# Sheet1.net
KiCad netlist of a schematic drawn in Altium Designer
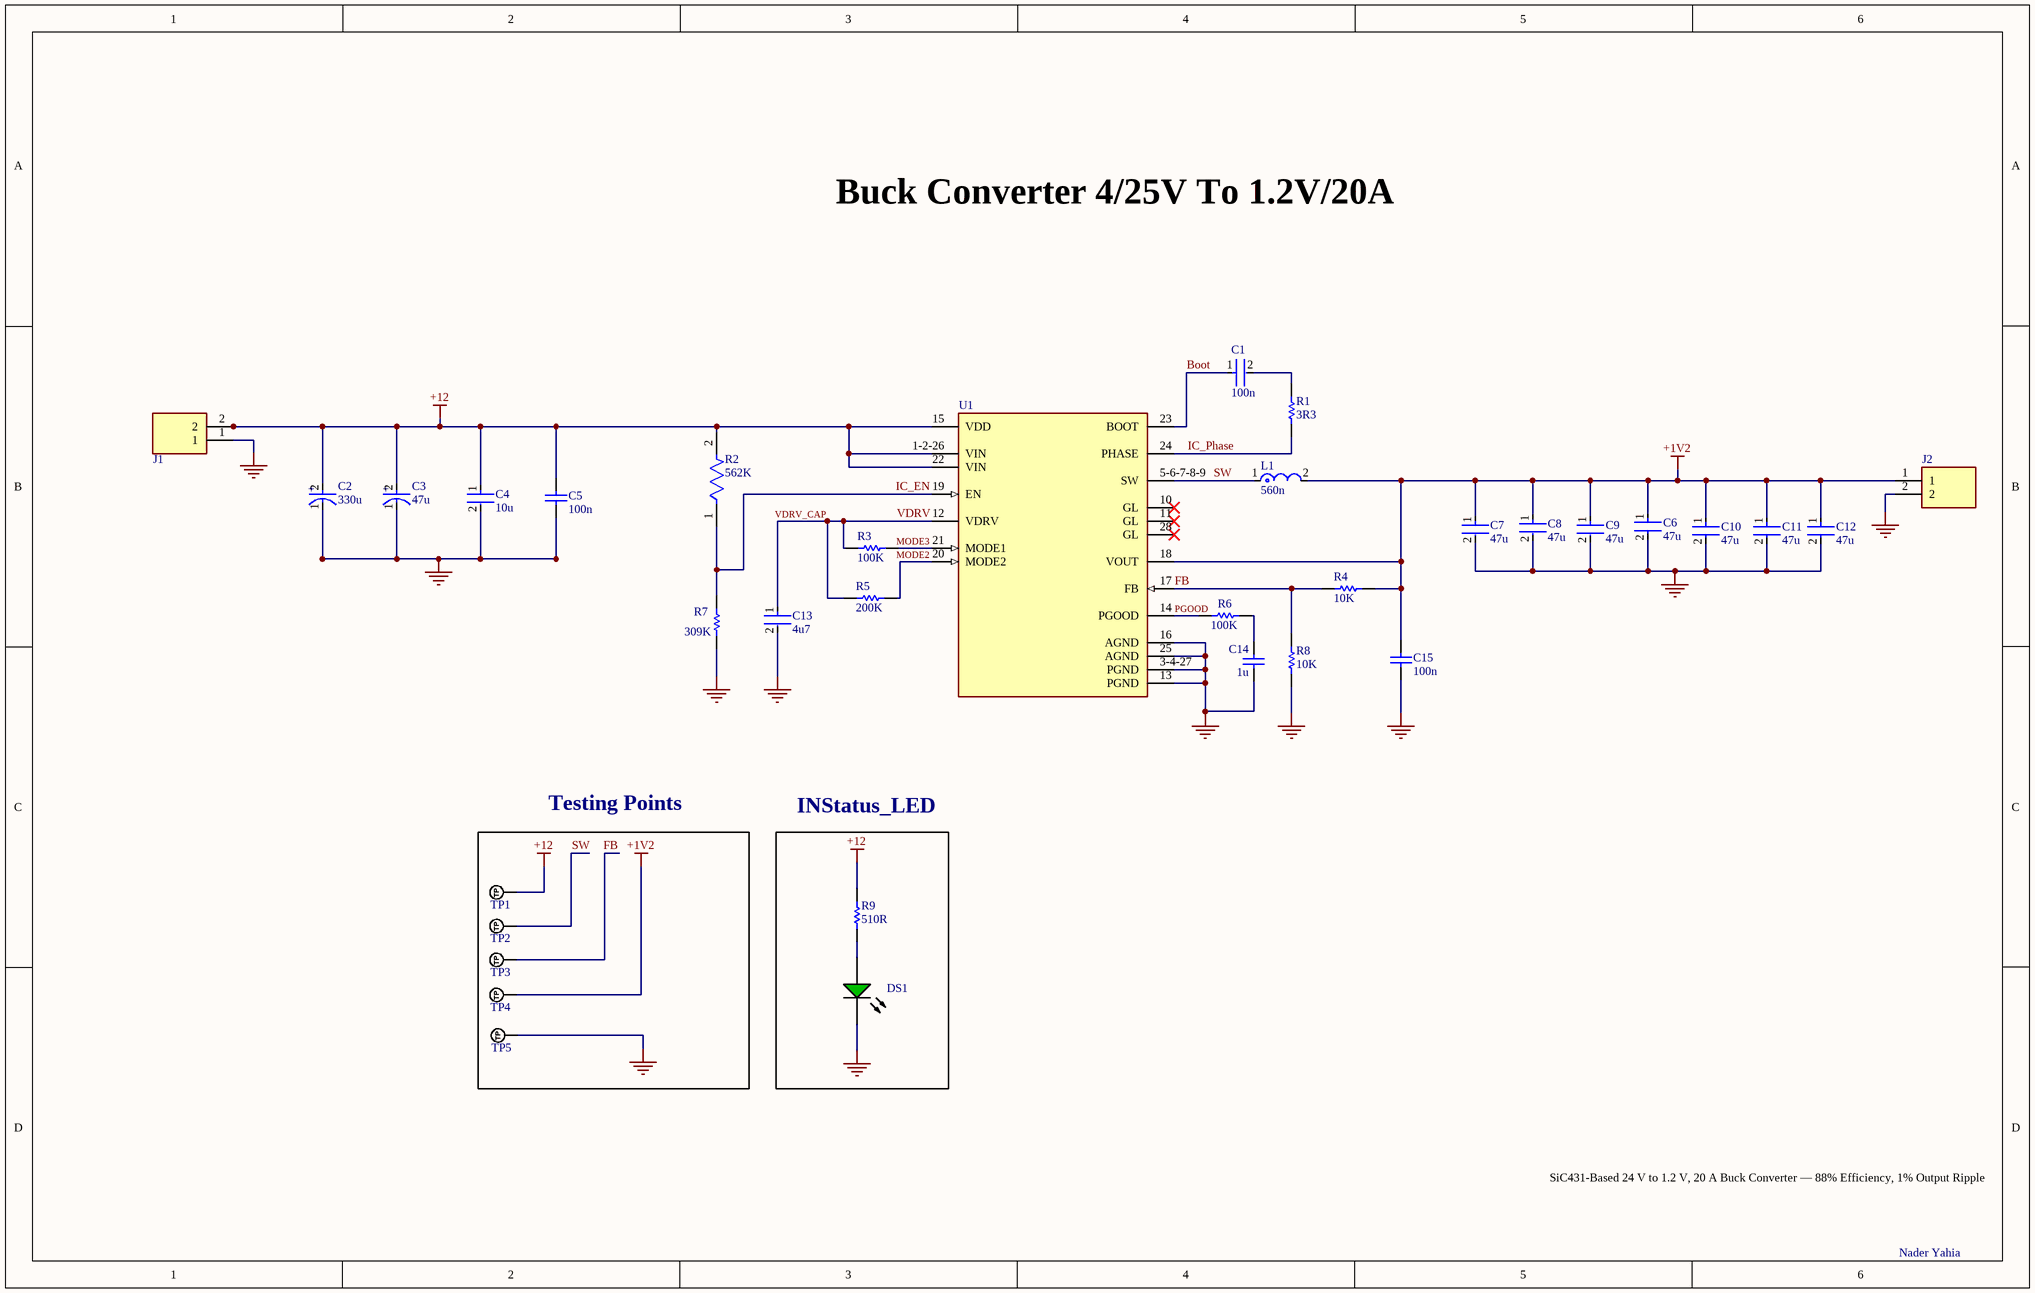
[diagram p0: Sheet1.SchDoc]

(export (version "E")
  (design (tool "Eeschema 10.0.6"))
  (components
    (comp (ref "C1")
      (value "100n")
      (footprint "FP-C0402-BB-MFG")
      (description "C0402 0.10 μF X5R 10.00% 10 V")
      (fields
        (field (name "MANUFACTURER_PART_NUMBER") "C0402C104K8PAC")
        (field (name "MANUFACTURER") "Kemet")
      )
      (libsource (lib "Altium Content Vault") (part "b4654b650e69147ec39a6b967a45e02"))
    )
    (comp (ref "C2")
      (value "330u")
      (footprint "FP-PCR1V331MCL1GS-MFG")
      (description "CAP ALUM POLY 330UF 20% 35V SMD")
      (fields
        (field (name "MANUFACTURER") "Nichicon")
        (field (name "OCTOPART") "https://octopart.com/pcr1v331mcl1gs-nichicon-34508554")
      )
      (libsource (lib "Altium Content Vault") (part "cf48714ba7e38822c1575c7ec0b6d1f"))
    )
    (comp (ref "C3")
      (value "47u")
      (footprint "FP-FPD-MFG")
      (description "CAP ALUM 47UF 20% 35V SMD")
      (fields (field (name "TOLERANCE") "20%") (field (name "VOLTAGE") "35V"))
      (libsource (lib "Altium Content Vault") (part "cf48714ba7e38822c1575c7ec0b6d1f"))
    )
    (comp (ref "C4")
      (value "10u")
      (footprint "FP-CL32-IPC_C")
      (description "Cap Ceramic 10uF 50V X7R ±10% SMD 1210 +125°C Embossed T/R")
      (fields (field (name "TOLERANCE") "10%") (field (name "VOLTAGE") "50V"))
      (libsource (lib "Altium Content Vault") (part "b4654b650e69147ec39a6b967a45e02"))
    )
    (comp (ref "C5")
      (value "100n")
      (footprint "CAPC1608X95X40NL15T15")
      (fields
        (field (name "MANUFACTURER") "Vitramon")
        (field (name "MANUFACTURER_PART_NUMBER") "VJ0603Y104KXJCW1BC")
      )
      (libsource (lib "Altium Content Vault") (part "CAP"))
    )
    (comp (ref "C6")
      (value "47u")
      (footprint "FP-GRM32E-0_3-0_2-IPC_A")
      (description "Chip Multilayer Ceramic Capacitors for General Purpose, 1210, 47uF, X7R, 15%, 10%, 10V")
      (fields (field (name "TOLERANCE") "10%") (field (name "VOLTAGE") "10V"))
      (libsource (lib "Altium Content Vault") (part "02cd4be3c70576c341d710602a673aa"))
    )
    (comp (ref "C7")
      (value "47u")
      (footprint "FP-GRM32E-0_3-0_2-IPC_A")
      (description "Chip Multilayer Ceramic Capacitors for General Purpose, 1210, 47uF, X7R, 15%, 10%, 10V")
      (fields (field (name "TOLERANCE") "10%") (field (name "VOLTAGE") "10V"))
      (libsource (lib "Altium Content Vault") (part "02cd4be3c70576c341d710602a673aa"))
    )
    (comp (ref "C8")
      (value "47u")
      (footprint "FP-GRM32E-0_3-0_2-IPC_A")
      (description "Chip Multilayer Ceramic Capacitors for General Purpose, 1210, 47uF, X7R, 15%, 10%, 10V")
      (fields (field (name "TOLERANCE") "10%") (field (name "VOLTAGE") "10V"))
      (libsource (lib "Altium Content Vault") (part "02cd4be3c70576c341d710602a673aa"))
    )
    (comp (ref "C9")
      (value "47u")
      (footprint "FP-GRM32E-0_3-0_2-IPC_A")
      (description "Chip Multilayer Ceramic Capacitors for General Purpose, 1210, 47uF, X7R, 15%, 10%, 10V")
      (fields (field (name "TOLERANCE") "10%") (field (name "VOLTAGE") "10V"))
      (libsource (lib "Altium Content Vault") (part "02cd4be3c70576c341d710602a673aa"))
    )
    (comp (ref "C10")
      (value "47u")
      (footprint "FP-GRM32E-0_3-0_2-IPC_A")
      (description "Chip Multilayer Ceramic Capacitors for General Purpose, 1210, 47uF, X7R, 15%, 10%, 10V")
      (fields (field (name "TOLERANCE") "10%") (field (name "VOLTAGE") "10V"))
      (libsource (lib "Altium Content Vault") (part "02cd4be3c70576c341d710602a673aa"))
    )
    (comp (ref "C11")
      (value "47u")
      (footprint "FP-GRM32E-0_3-0_2-IPC_A")
      (description "Chip Multilayer Ceramic Capacitors for General Purpose, 1210, 47uF, X7R, 15%, 10%, 10V")
      (fields (field (name "TOLERANCE") "10%") (field (name "VOLTAGE") "10V"))
      (libsource (lib "Altium Content Vault") (part "02cd4be3c70576c341d710602a673aa"))
    )
    (comp (ref "C12")
      (value "47u")
      (footprint "FP-GRM32E-0_3-0_2-IPC_A")
      (description "Chip Multilayer Ceramic Capacitors for General Purpose, 1210, 47uF, X7R, 15%, 10%, 10V")
      (fields (field (name "TOLERANCE") "10%") (field (name "VOLTAGE") "10V"))
      (libsource (lib "Altium Content Vault") (part "02cd4be3c70576c341d710602a673aa"))
    )
    (comp (ref "C13")
      (value "4u7")
      (footprint "FP-CC0603-DA-MFG")
      (description "CAP CER 4.7UF 6.3V X5R 0603")
      (fields (field (name "TOLERANCE") "0.1") (field (name "MANUFACTURER_PART_NUMBER") "CC0603KRX5R5BB475"))
      (libsource (lib "Altium Content Vault") (part "11868f565c42a9108669ba33697ecf6"))
    )
    (comp (ref "C14")
      (value "1u")
      (footprint "CAPC1608X95X40NL15T15")
      (fields
        (field (name "MANUFACTURER") "Vitramon")
        (field (name "MANUFACTURER_PART_NUMBER") "VJ0603G105KXYCW1BC")
      )
      (libsource (lib "Altium Content Vault") (part "CAP"))
    )
    (comp (ref "C15")
      (value "100n")
      (footprint "CAPC1608X95X40NL15T15")
      (fields
        (field (name "MANUFACTURER") "Vitramon")
        (field (name "MANUFACTURER_PART_NUMBER") "VJ0603Y104KXJCW1BC")
      )
      (libsource (lib "Altium Content Vault") (part "CAP"))
    )
    (comp (ref "DS1")
      (value "LTST-C170KGKT")
      (footprint "LTST-LTST-C170KGKT-2_V")
      (description "Ultra Bright AlInGaP Chip LED, 75 mW, -55 to 85 degC, 2-Pin SMD (0805), RoHS, Tape and Reel")
      (fields (field (name "MANUFACTURER") "Lite-On"))
      (libsource (lib "Altium Content Vault") (part "LED-GREEN-KA-2"))
    )
    (comp (ref "J1")
      (value "TB005-762-02BE")
      (footprint "SamacSys:TB00576202BE")
      (description "Connector")
      (fields (field (name "MOUSER PART NUMBER") "490-TB005-762-02BE"))
      (libsource (lib "") (part "TB005-762-02BE_1"))
    )
    (comp (ref "J2")
      (value "TB005-762-02BE")
      (footprint "SamacSys:TB00576202BE")
      (description "Connector")
      (fields (field (name "MOUSER PART NUMBER") "490-TB005-762-02BE"))
      (libsource (lib "*") (part "TB005-762-02BE"))
    )
    (comp (ref "L1")
      (value "560n")
      (footprint "FP-FCUL1060-MFG")
      (description "FIXED IND")
      (fields (field (name "MANUFACTURER_PART_NUMBER") "FCUL1060-H-R56M=P3"))
      (libsource (lib "Altium Content Vault") (part "4cc4b267dca4c8e51f7102f422741d8"))
    )
    (comp (ref "R1")
      (value "3R3")
      (footprint "RESC1005X40X25LL05T10")
      (fields
        (field (name "MANUFACTURER_PART_NUMBER") "RC0402FR-0733RL")
        (field (name "MANUFACTURER") "Yageo / Phycomp")
      )
      (libsource (lib "Altium Content Vault") (part "RES"))
    )
    (comp (ref "R2")
      (value "562K")
      (footprint "FP-CRCW0402-e3-MFG")
      (description "RES Thick Film, 562kΩ, 1%, 0.063W, 100ppm/°C, 0402")
      (fields (field (name "TOLERANCE") "1%") (field (name "MANUFACTURER_PART_NUMBER") "CRCW0402562KFKED"))
      (libsource (lib "Altium Content Vault") (part "1029c3af85768c4190bb7ad29bc67b5"))
    )
    (comp (ref "R3")
      (value "100K")
      (footprint "RESC1005X40X25NL05T10")
      (fields
        (field (name "MANUFACTURER_PART_NUMBER") "RC0402FR-07100KL")
        (field (name "MANUFACTURER") "Yageo / Phycomp")
      )
      (libsource (lib "Altium Content Vault") (part "RES"))
    )
    (comp (ref "R4")
      (value "10K")
      (footprint "RESC1609X50X30NL8T20")
      (description "Chip Resistor, 10 KOhm, +/- 1%, 100 mW, -55 to 155 degC, 0603 (1608 Metric), RoHS, Tape and Reel")
      (fields
        (field (name "MANUFACTURER") "Vishay Semiconductor")
        (field (name "MANUFACTURER_PART_NUMBER") "CRCW060310K0FKEA")
      )
      (libsource (lib "Altium Content Vault") (part "RES-2"))
    )
    (comp (ref "R5")
      (value "200K")
      (footprint "RESC1005X40X25LL05T10")
      (fields
        (field (name "MANUFACTURER_PART_NUMBER") "RC0402FR-07200KL")
        (field (name "MANUFACTURER") "Yageo / Phycomp")
      )
      (libsource (lib "Altium Content Vault") (part "RES"))
    )
    (comp (ref "R6")
      (value "100K")
      (footprint "RESC1005X40X25NL05T10")
      (fields
        (field (name "MANUFACTURER_PART_NUMBER") "RC0402FR-07100KL")
        (field (name "MANUFACTURER") "Yageo / Phycomp")
      )
      (libsource (lib "Altium Content Vault") (part "RES"))
    )
    (comp (ref "R7")
      (value "309K")
      (footprint "RESC1005X40X25LL05T10")
      (fields
        (field (name "MANUFACTURER") "Yageo")
        (field (name "MANUFACTURER_PART_NUMBER") "RC0402FR-07309KL")
      )
      (libsource (lib "Altium Content Vault") (part "RES"))
    )
    (comp (ref "R8")
      (value "10K")
      (footprint "RESC1609X50X30NL8T20")
      (description "Chip Resistor, 10 KOhm, +/- 1%, 100 mW, -55 to 155 degC, 0603 (1608 Metric), RoHS, Tape and Reel")
      (fields
        (field (name "MANUFACTURER") "Vishay Semiconductor")
        (field (name "MANUFACTURER_PART_NUMBER") "CRCW060310K0FKEA")
      )
      (libsource (lib "Altium Content Vault") (part "RES-2"))
    )
    (comp (ref "R9")
      (value "510R")
      (footprint "RESC3116X65X40LL10T20")
      (fields (field (name "MANUFACTURER_PART_NUMBER") "RC1206JR-07510RL"))
      (libsource (lib "Altium Content Vault") (part "RES"))
    )
    (comp (ref "TP1")
      (value "TP_VIN")
      (footprint "PAD_RND_1MM")
      (description "Test Point Round 1mm (NO BOM)")
      (libsource (lib "Schlib1") (part "TEST_POINT_RND_1MM"))
    )
    (comp (ref "TP2")
      (value "TP_NOBOM")
      (footprint "PAD_RND_1MM")
      (description "Test Point Round 1mm (NO BOM)")
      (libsource (lib "Schlib1") (part "TEST_POINT_RND_1MM"))
    )
    (comp (ref "TP3")
      (value "TP_NOBOM")
      (footprint "PAD_RND_1MM")
      (description "Test Point Round 1mm (NO BOM)")
      (libsource (lib "Schlib1") (part "TEST_POINT_RND_1MM"))
    )
    (comp (ref "TP4")
      (value "TP_NOBOM")
      (footprint "PAD_RND_1MM")
      (description "Test Point Round 1mm (NO BOM)")
      (libsource (lib "Schlib1") (part "TEST_POINT_RND_1MM"))
    )
    (comp (ref "TP5")
      (value "TP_NOBOM")
      (footprint "PAD_RND_1MM")
      (description "Test Point Round 1mm (NO BOM)")
      (libsource (lib "Schlib1") (part "TEST_POINT_RND_1MM"))
    )
    (comp (ref "U1")
      (value "SIC431AED-T1-GE3")
      (footprint "FP-T22-0442-MFG")
      (description "SIC431AED-T1-GE3 IC Reg Buck Adj 24A MLP44-24")
      (libsource (lib "Altium Content Vault") (part "40dafd62ff4b33f9f37e65bbcadf93f"))
    )
  )
  (nets
    (net (code "1") (name "+1V2") (class "Default")
      (node (ref "C10") (pin "1") (pinfunction "1_1") (pintype "passive"))
      (node (ref "C11") (pin "1") (pinfunction "1_1") (pintype "passive"))
      (node (ref "C12") (pin "1") (pinfunction "1_1") (pintype "passive"))
      (node (ref "C15") (pin "2") (pinfunction "2_2") (pintype "passive"))
      (node (ref "C6") (pin "1") (pinfunction "1_1") (pintype "passive"))
      (node (ref "C7") (pin "1") (pinfunction "1_1") (pintype "passive"))
      (node (ref "C8") (pin "1") (pinfunction "1_1") (pintype "passive"))
      (node (ref "C9") (pin "1") (pinfunction "1_1") (pintype "passive"))
      (node (ref "J2") (pin "1") (pinfunction "1_1") (pintype "passive"))
      (node (ref "L1") (pin "2") (pinfunction "2_2") (pintype "passive"))
      (node (ref "R4") (pin "1") (pinfunction "1_1") (pintype "passive"))
      (node (ref "TP4") (pin "1") (pinfunction "TP_1") (pintype "passive"))
      (node (ref "U1") (pin "18") (pinfunction "VOUT_18") (pintype "passive"))
    )
    (net (code "2") (name "+12") (class "Default")
      (node (ref "C2") (pin "2") (pinfunction "A_2") (pintype "passive"))
      (node (ref "C3") (pin "2") (pinfunction "A_2") (pintype "passive"))
      (node (ref "C4") (pin "1") (pinfunction "1_1") (pintype "passive"))
      (node (ref "C5") (pin "2") (pinfunction "2_2") (pintype "passive"))
      (node (ref "J1") (pin "2") (pinfunction "2_2") (pintype "passive"))
      (node (ref "R2") (pin "2") (pinfunction "2_2") (pintype "passive"))
      (node (ref "R9") (pin "2") (pinfunction "2_2") (pintype "passive"))
      (node (ref "TP1") (pin "1") (pinfunction "TP_1") (pintype "passive"))
      (node (ref "U1") (pin "1-2-26") (pinfunction "VIN_1-2-26") (pintype "power_in"))
      (node (ref "U1") (pin "15") (pinfunction "VDD_15") (pintype "power_in"))
      (node (ref "U1") (pin "22") (pinfunction "VIN_22") (pintype "power_in"))
    )
    (net (code "3") (name "/Boot") (class "Default")
      (node (ref "C1") (pin "1") (pinfunction "1_1") (pintype "passive"))
      (node (ref "U1") (pin "23") (pinfunction "BOOT_23") (pintype "passive"))
    )
    (net (code "4") (name "/FB") (class "Default")
      (node (ref "R4") (pin "2") (pinfunction "2_2") (pintype "passive"))
      (node (ref "R8") (pin "2") (pinfunction "2_2") (pintype "passive"))
      (node (ref "TP3") (pin "1") (pinfunction "TP_1") (pintype "passive"))
      (node (ref "U1") (pin "17") (pinfunction "FB_17") (pintype "input"))
    )
    (net (code "5") (name "/IC_EN") (class "Default")
      (node (ref "R2") (pin "1") (pinfunction "1_1") (pintype "passive"))
      (node (ref "R7") (pin "2") (pinfunction "2_2") (pintype "passive"))
      (node (ref "U1") (pin "19") (pinfunction "EN_19") (pintype "input"))
    )
    (net (code "6") (name "/IC_Phase") (class "Default")
      (node (ref "R1") (pin "1") (pinfunction "1_1") (pintype "passive"))
      (node (ref "U1") (pin "24") (pinfunction "PHASE_24") (pintype "passive"))
    )
    (net (code "7") (name "/MODE2") (class "Default")
      (node (ref "R5") (pin "1") (pinfunction "1_1") (pintype "passive"))
      (node (ref "U1") (pin "20") (pinfunction "MODE2_20") (pintype "input"))
    )
    (net (code "8") (name "/MODE3") (class "Default")
      (node (ref "R3") (pin "2") (pinfunction "2_2") (pintype "passive"))
      (node (ref "U1") (pin "21") (pinfunction "MODE1_21") (pintype "input"))
    )
    (net (code "9") (name "/PGOOD") (class "Default")
      (node (ref "R6") (pin "1") (pinfunction "1_1") (pintype "passive"))
      (node (ref "U1") (pin "14") (pinfunction "PGOOD_14") (pintype "open_collector"))
    )
    (net (code "10") (name "/SW") (class "Default")
      (node (ref "L1") (pin "1") (pinfunction "1_1") (pintype "passive"))
      (node (ref "TP2") (pin "1") (pinfunction "TP_1") (pintype "passive"))
      (node (ref "U1") (pin "5-6-7-8-9") (pinfunction "SW_5-6-7-8-9") (pintype "passive"))
    )
    (net (code "11") (name "/VDRV") (class "Default")
      (node (ref "C13") (pin "1") (pinfunction "1_1") (pintype "passive"))
      (node (ref "R3") (pin "1") (pinfunction "1_1") (pintype "passive"))
      (node (ref "R5") (pin "2") (pinfunction "2_2") (pintype "passive"))
      (node (ref "U1") (pin "12") (pinfunction "VDRV_12") (pintype "passive"))
    )
    (net (code "12") (name "GND") (class "Default")
      (node (ref "C10") (pin "2") (pinfunction "2_2") (pintype "passive"))
      (node (ref "C11") (pin "2") (pinfunction "2_2") (pintype "passive"))
      (node (ref "C12") (pin "2") (pinfunction "2_2") (pintype "passive"))
      (node (ref "C13") (pin "2") (pinfunction "2_2") (pintype "passive"))
      (node (ref "C14") (pin "1") (pinfunction "1_1") (pintype "passive"))
      (node (ref "C15") (pin "1") (pinfunction "1_1") (pintype "passive"))
      (node (ref "C2") (pin "1") (pinfunction "C_1") (pintype "passive"))
      (node (ref "C3") (pin "1") (pinfunction "C_1") (pintype "passive"))
      (node (ref "C4") (pin "2") (pinfunction "2_2") (pintype "passive"))
      (node (ref "C5") (pin "1") (pinfunction "1_1") (pintype "passive"))
      (node (ref "C6") (pin "2") (pinfunction "2_2") (pintype "passive"))
      (node (ref "C7") (pin "2") (pinfunction "2_2") (pintype "passive"))
      (node (ref "C8") (pin "2") (pinfunction "2_2") (pintype "passive"))
      (node (ref "C9") (pin "2") (pinfunction "2_2") (pintype "passive"))
      (node (ref "DS1") (pin "1") (pinfunction "K_1") (pintype "passive"))
      (node (ref "J1") (pin "1") (pinfunction "1_1") (pintype "passive"))
      (node (ref "J2") (pin "2") (pinfunction "2_2") (pintype "passive"))
      (node (ref "R7") (pin "1") (pinfunction "1_1") (pintype "passive"))
      (node (ref "R8") (pin "1") (pinfunction "1_1") (pintype "passive"))
      (node (ref "TP5") (pin "1") (pinfunction "TP_1") (pintype "passive"))
      (node (ref "U1") (pin "13") (pinfunction "PGND_13") (pintype "power_in"))
      (node (ref "U1") (pin "16") (pinfunction "AGND_16") (pintype "power_in"))
      (node (ref "U1") (pin "25") (pinfunction "AGND_25") (pintype "power_in"))
      (node (ref "U1") (pin "3-4-27") (pinfunction "PGND_3-4-27") (pintype "power_in"))
    )
    (net (code "13") (name "Net-(C1-Pad2)") (class "Default")
      (node (ref "C1") (pin "2") (pinfunction "2_2") (pintype "passive"))
      (node (ref "R1") (pin "2") (pinfunction "2_2") (pintype "passive"))
    )
    (net (code "14") (name "Net-(C14-Pad2)") (class "Default")
      (node (ref "C14") (pin "2") (pinfunction "2_2") (pintype "passive"))
      (node (ref "R6") (pin "2") (pinfunction "2_2") (pintype "passive"))
    )
    (net (code "15") (name "Net-(DS1-A)") (class "Default")
      (node (ref "DS1") (pin "2") (pinfunction "A_2") (pintype "passive"))
      (node (ref "R9") (pin "1") (pinfunction "1_1") (pintype "passive"))
    )
    (net (code "16") (name "unconnected-(U1-GL-Pad10)") (class "Default")
      (node (ref "U1") (pin "10") (pinfunction "GL_10") (pintype "passive+no_connect"))
    )
    (net (code "17") (name "unconnected-(U1-GL-Pad11)") (class "Default")
      (node (ref "U1") (pin "11") (pinfunction "GL_11") (pintype "passive+no_connect"))
    )
    (net (code "18") (name "unconnected-(U1-GL-Pad28)") (class "Default")
      (node (ref "U1") (pin "28") (pinfunction "GL_28") (pintype "passive+no_connect"))
    )
  )
)
